# senseBox-HDC1080_v20.net
KiCad netlist of a schematic drawn in EAGLE
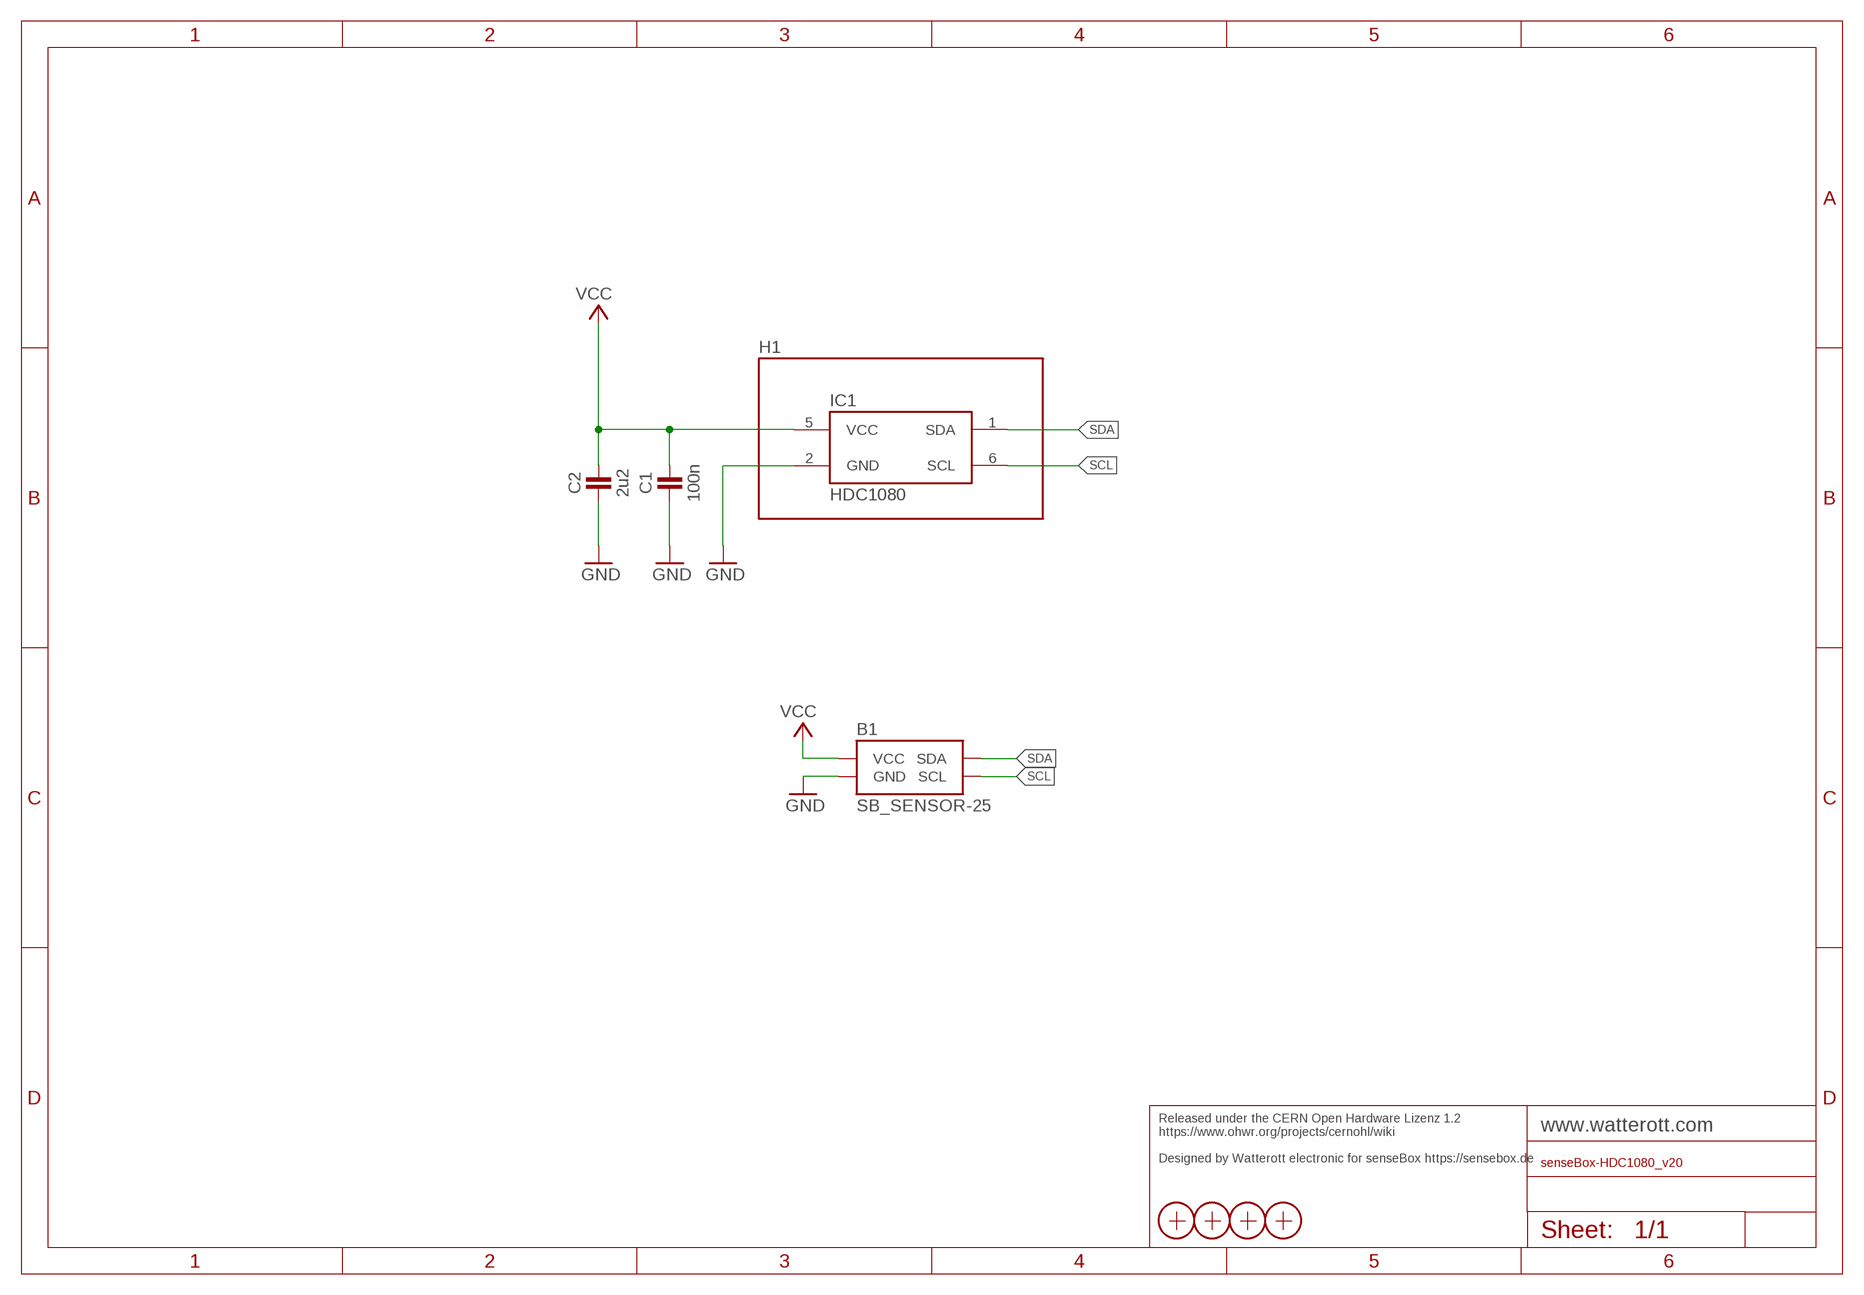
[diagram p0: schematic, sheet 1]

(export (version "E")
  (design (tool "Eeschema 10.0.6"))
  (components
    (comp (ref "B1")
      (value "SB_SENSOR-25")
      (footprint "eagle-import:SB-25X25")
      (libsource (lib "eagle-import") (part "SB_SENSOR-25"))
    )
    (comp (ref "C1")
      (value "100n")
      (footprint "eagle-import:C0402")
      (libsource (lib "eagle-import") (part "CAPACITOR-0402"))
    )
    (comp (ref "C2")
      (value "2u2")
      (footprint "eagle-import:C0402")
      (libsource (lib "eagle-import") (part "CAPACITOR-0402"))
    )
    (comp (ref "H1")
      (value "SF2")
      (footprint "eagle-import:SF2")
      (libsource (lib "eagle-import") (part "SF2"))
    )
    (comp (ref "IC1")
      (value "HDC1080")
      (footprint "eagle-import:WSON6")
      (libsource (lib "eagle-import") (part "HDC1080"))
    )
    (comp (ref "X1")
      (value "PASSER-07")
      (footprint "eagle-import:PASSER_07MM")
      (libsource (lib "eagle-import") (part "PASSER-07"))
    )
    (comp (ref "X2")
      (value "PASSER-07")
      (footprint "eagle-import:PASSER_07MM")
      (libsource (lib "eagle-import") (part "PASSER-07"))
    )
    (comp (ref "X3")
      (value "PASSER-07")
      (footprint "eagle-import:PASSER_07MM")
      (libsource (lib "eagle-import") (part "PASSER-07"))
    )
    (comp (ref "X4")
      (value "PASSER-07")
      (footprint "eagle-import:PASSER_07MM")
      (libsource (lib "eagle-import") (part "PASSER-07"))
    )
  )
  (nets
    (net (code "1") (name "GND") (class "Default")
      (node (ref "B1") (pin "GND") (pinfunction "GND_GND") (pintype "power_in"))
      (node (ref "C1") (pin "1") (pinfunction "1_1") (pintype "passive"))
      (node (ref "C2") (pin "1") (pinfunction "1_1") (pintype "passive"))
      (node (ref "IC1") (pin "2") (pinfunction "GND_2") (pintype "power_in"))
    )
    (net (code "2") (name "SCL") (class "Default")
      (node (ref "B1") (pin "SCL") (pinfunction "SCL_SCL") (pintype "bidirectional"))
      (node (ref "IC1") (pin "6") (pinfunction "SCL_6") (pintype "bidirectional"))
    )
    (net (code "3") (name "SDA") (class "Default")
      (node (ref "B1") (pin "SDA") (pinfunction "SDA_SDA") (pintype "bidirectional"))
      (node (ref "IC1") (pin "1") (pinfunction "SDA_1") (pintype "bidirectional"))
    )
    (net (code "4") (name "VCC") (class "Default")
      (node (ref "B1") (pin "VCC") (pinfunction "VCC_VCC") (pintype "power_in"))
      (node (ref "C1") (pin "2") (pinfunction "2_2") (pintype "passive"))
      (node (ref "C2") (pin "2") (pinfunction "2_2") (pintype "passive"))
      (node (ref "IC1") (pin "5") (pinfunction "VCC_5") (pintype "power_in"))
    )
  )
)
